# 1-Schematic_USB_project.net
KiCad netlist of a schematic drawn in EasyEDA
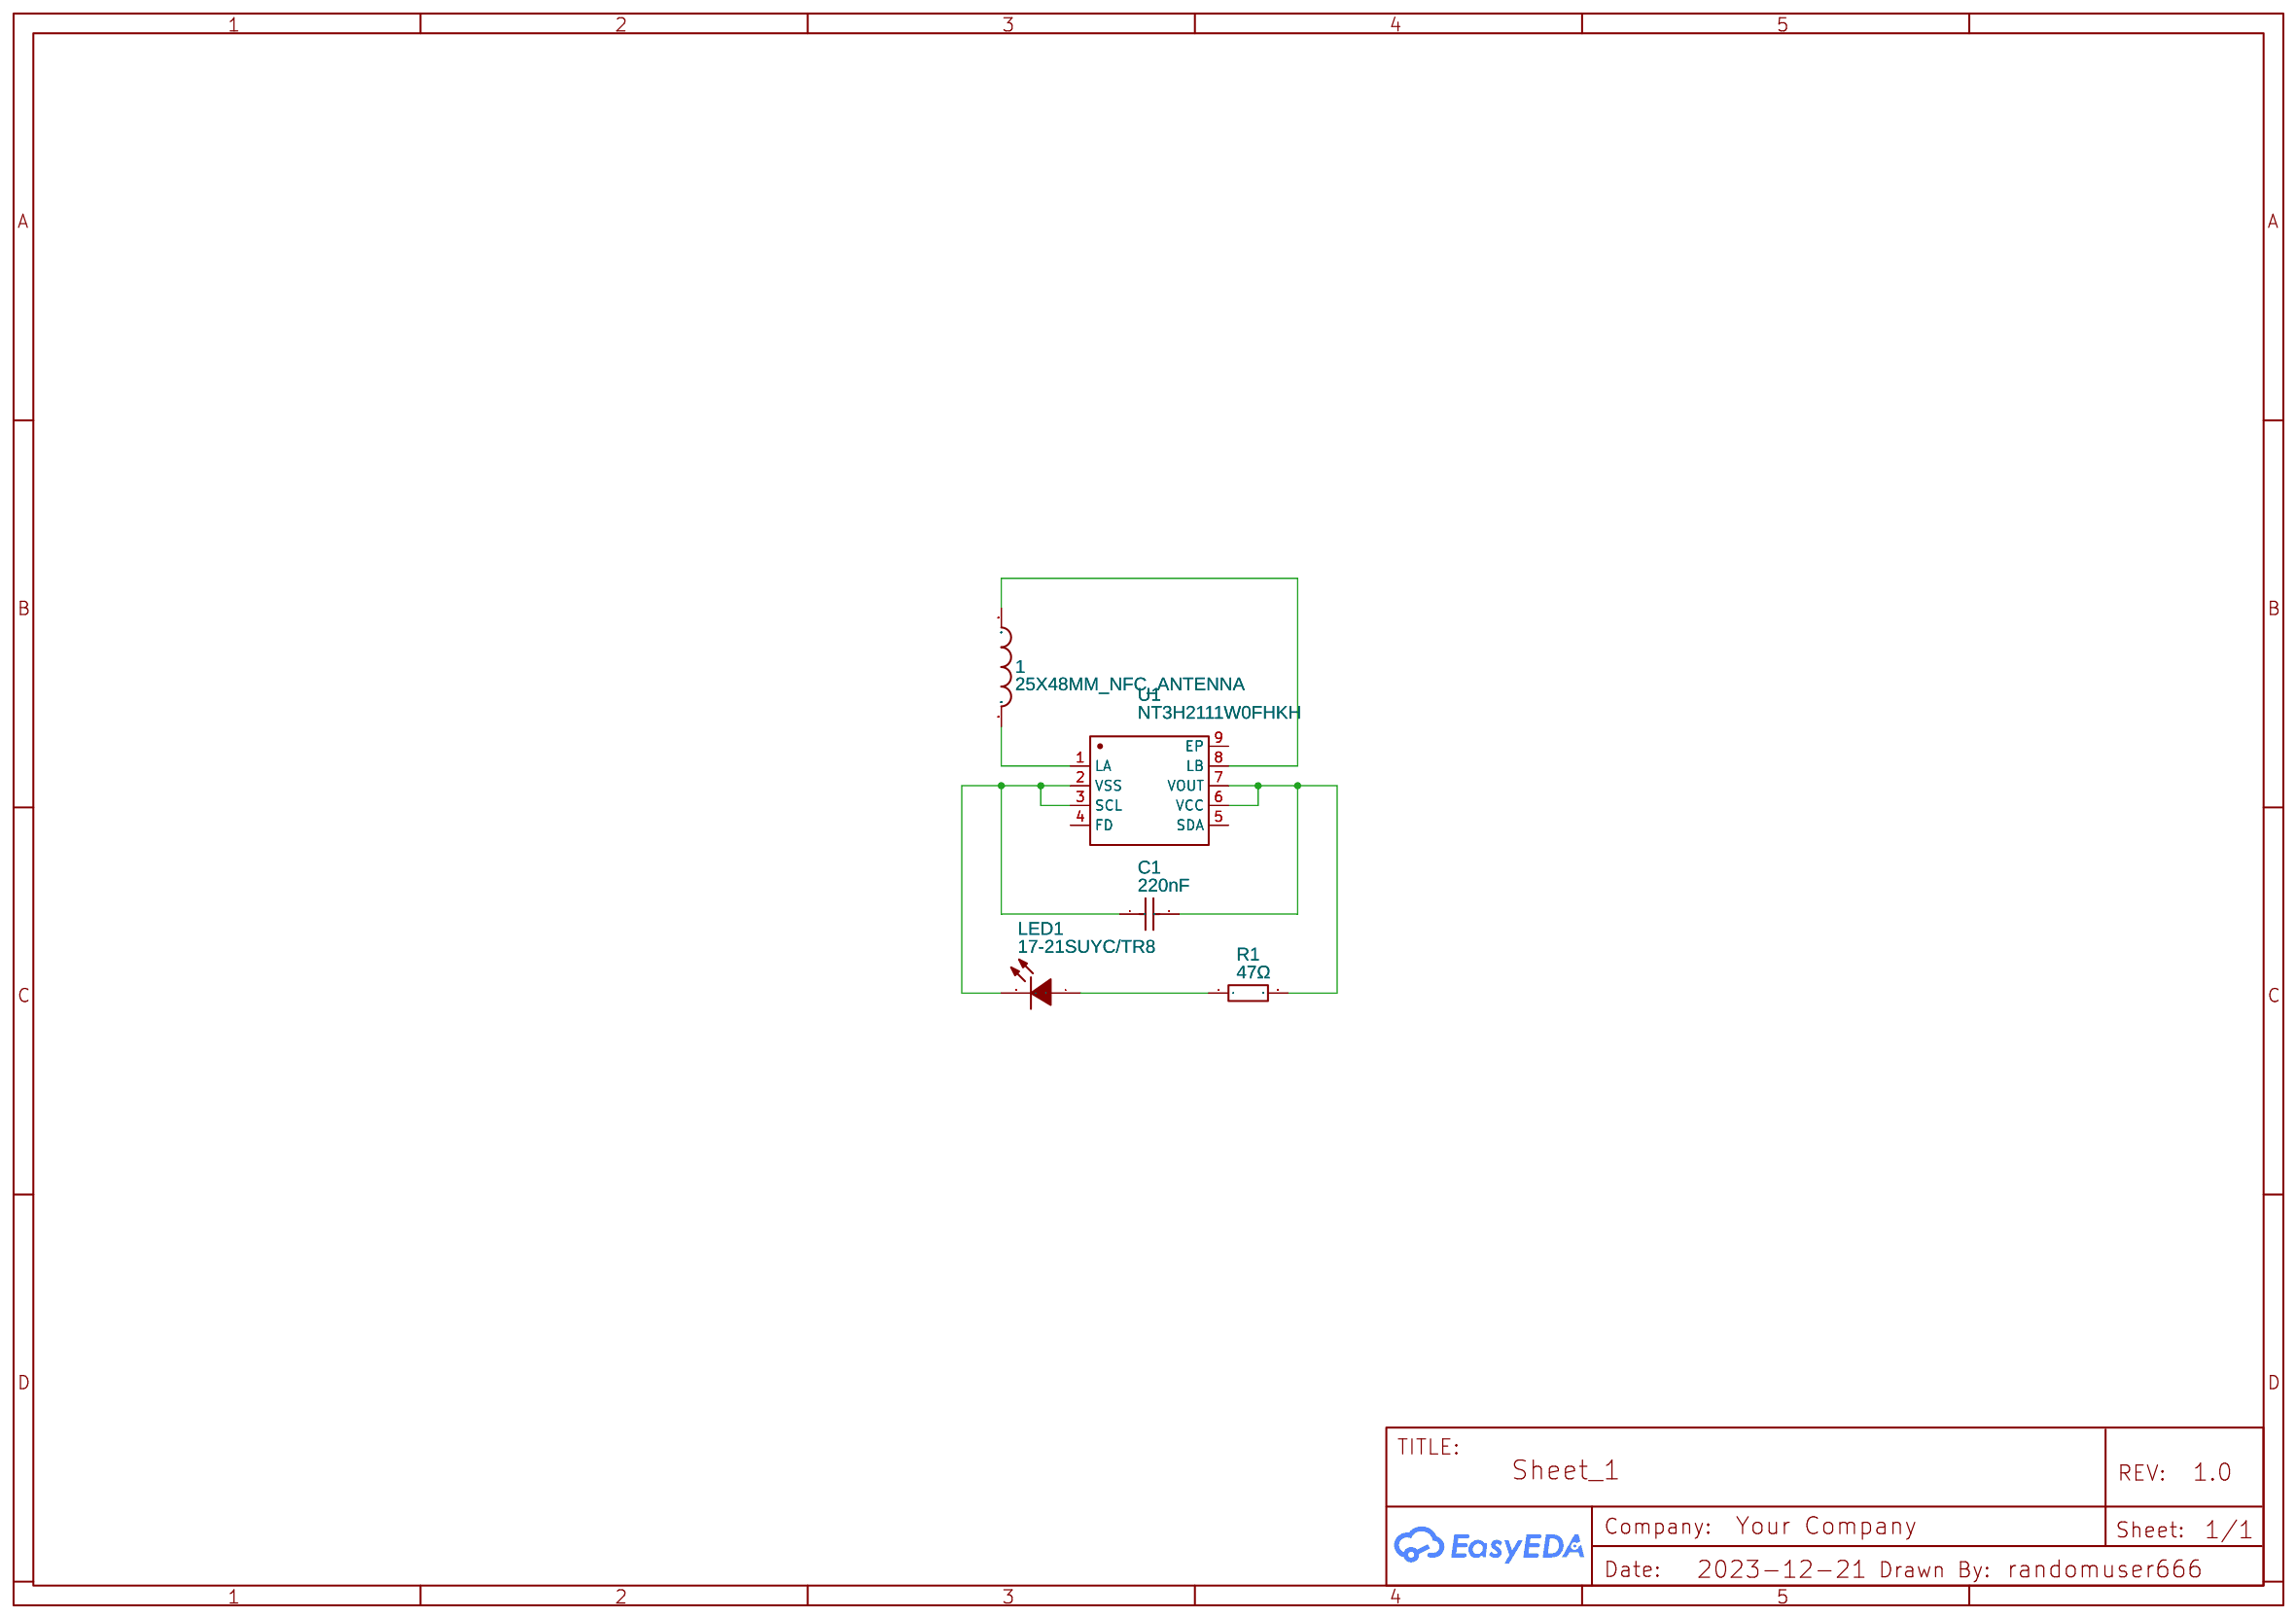
[diagram p0: schematic sheet]

(export (version "E")
  (design (tool "Eeschema 10.0.6"))
  (components
    (comp (ref "1") (value "25X48MM_NFC_ANTENNA") (libsource (lib "") (part "25X48MM_NFC_ANTENNA")))
    (comp (ref "C1")
      (value "220nF")
      (fields
        (field (name "Manufacturer Part") "CL10B224KA8NNNC")
        (field (name "Manufacturer") "SAMSUNG(三星)")
      )
      (libsource (lib "") (part "CL10B224KA8NNNC"))
    )
    (comp (ref "LED1")
      (value "17-21SUYC/TR8")
      (fields (field (name "Manufacturer Part") "KT-0805黄灯") (field (name "Manufacturer") "KENTO"))
      (libsource (lib "") (part "17-21SUYC/TR8"))
    )
    (comp (ref "R1")
      (value "47Ω")
      (fields
        (field (name "Manufacturer Part") "0603WAF470JT5E")
        (field (name "Manufacturer") "UNI-ROYAL(厚声)")
      )
      (libsource (lib "") (part "0603WAF470JT5E"))
    )
    (comp (ref "U1")
      (value "NT3H2111W0FHKH")
      (fields (field (name "Manufacturer") "NXP(恩智浦)"))
      (libsource (lib "") (part "NT3H2111W0FHKH"))
    )
  )
  (nets
    (net (code "1") (name "Net-(LED1-+)") (class "Default")
      (node (ref "LED1") (pin "1") (pinfunction "+_1") (pintype "unspecified"))
      (node (ref "R1") (pin "1") (pinfunction "1_1") (pintype "input"))
    )
    (net (code "2") (name "Net-(LED1--)") (class "Default")
      (node (ref "C1") (pin "1") (pinfunction "1_1") (pintype "input"))
      (node (ref "LED1") (pin "2") (pinfunction "-_2") (pintype "unspecified"))
      (node (ref "U1") (pin "2") (pinfunction "VSS_2") (pintype "unspecified"))
      (node (ref "U1") (pin "3") (pinfunction "SCL_3") (pintype "unspecified"))
    )
    (net (code "3") (name "Net-(U1-LA)") (class "Default")
      (node (ref "1") (pin "P$2") (pinfunction "P$2_P$2") (pintype "bidirectional"))
      (node (ref "U1") (pin "1") (pinfunction "LA_1") (pintype "unspecified"))
    )
    (net (code "4") (name "Net-(U1-LB)") (class "Default")
      (node (ref "1") (pin "P$1") (pinfunction "P$1_P$1") (pintype "bidirectional"))
      (node (ref "U1") (pin "8") (pinfunction "LB_8") (pintype "unspecified"))
    )
    (net (code "5") (name "Net-(U1-VCC)") (class "Default")
      (node (ref "C1") (pin "2") (pinfunction "2_2") (pintype "input"))
      (node (ref "R1") (pin "2") (pinfunction "2_2") (pintype "input"))
      (node (ref "U1") (pin "6") (pinfunction "VCC_6") (pintype "unspecified"))
      (node (ref "U1") (pin "7") (pinfunction "VOUT_7") (pintype "unspecified"))
    )
    (net (code "6") (name "unconnected-(U1-EP-Pad9)") (class "Default")
      (node (ref "U1") (pin "9") (pinfunction "EP_9") (pintype "unspecified"))
    )
    (net (code "7") (name "unconnected-(U1-FD-Pad4)") (class "Default")
      (node (ref "U1") (pin "4") (pinfunction "FD_4") (pintype "unspecified"))
    )
    (net (code "8") (name "unconnected-(U1-SDA-Pad5)") (class "Default")
      (node (ref "U1") (pin "5") (pinfunction "SDA_5") (pintype "unspecified"))
    )
  )
)
